# Mabee_DHT11_sensor_V1_1.net
KiCad netlist of a schematic drawn in EAGLE
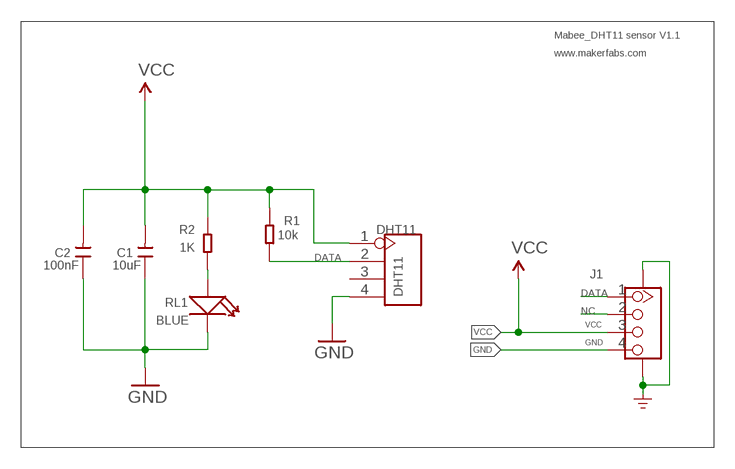
[diagram p0: schematic, sheet 1]

(export (version "E")
  (design (tool "Eeschema 10.0.6"))
  (components
    (comp (ref "C1")
      (value "10uF")
      (footprint "eagle-import:0603")
      (libsource (lib "eagle-import") (part "C-0603"))
    )
    (comp (ref "C2")
      (value "100nF")
      (footprint "eagle-import:0603")
      (libsource (lib "eagle-import") (part "C-0603"))
    )
    (comp (ref "DHT11")
      (value "DHT11")
      (footprint "eagle-import:4P-65_35ROUND")
      (libsource (lib "eagle-import") (part "HEADER-4P-60/35MILROUND"))
    )
    (comp (ref "J1")
      (value "GROVE-CONNECTOR-SMD'90D'")
      (footprint "eagle-import:HW4-SMD-2.0-90D")
      (libsource (lib "eagle-import") (part "GROVE-CONNECTOR-SMD'90D'"))
    )
    (comp (ref "R1")
      (value "10k")
      (footprint "eagle-import:R0603")
      (libsource (lib "eagle-import") (part "R-0603"))
    )
    (comp (ref "R2")
      (value "1K")
      (footprint "eagle-import:R0603")
      (libsource (lib "eagle-import") (part "R-0603"))
    )
    (comp (ref "RL1")
      (value "BLUE")
      (footprint "eagle-import:LED-0603")
      (libsource (lib "eagle-import") (part "LED'0603'"))
    )
  )
  (nets
    (net (code "1") (name "/DATA") (class "Default")
      (node (ref "DHT11") (pin "2") (pinfunction "P$2_2") (pintype "bidirectional"))
      (node (ref "J1") (pin "1") (pinfunction "1_1") (pintype "bidirectional"))
      (node (ref "R1") (pin "1") (pinfunction "1_1") (pintype "passive"))
    )
    (net (code "2") (name "/NC") (class "Default")
      (node (ref "J1") (pin "2") (pinfunction "2_2") (pintype "bidirectional"))
    )
    (net (code "3") (name "GND") (class "Default")
      (node (ref "C1") (pin "1") (pinfunction "1_1") (pintype "passive"))
      (node (ref "C2") (pin "1") (pinfunction "1_1") (pintype "passive"))
      (node (ref "DHT11") (pin "4") (pinfunction "P$4_4") (pintype "bidirectional"))
      (node (ref "J1") (pin "4") (pinfunction "4_4") (pintype "bidirectional"))
      (node (ref "J1") (pin "SS1") (pinfunction "SS1_SS1") (pintype "bidirectional"))
      (node (ref "J1") (pin "SS2") (pinfunction "SS2_SS2") (pintype "bidirectional"))
      (node (ref "RL1") (pin "-") (pinfunction "-_-") (pintype "passive"))
    )
    (net (code "4") (name "Net-(R2-Pad2)") (class "Default")
      (node (ref "R2") (pin "2") (pinfunction "2_2") (pintype "passive"))
      (node (ref "RL1") (pin "+") (pinfunction "+_+") (pintype "passive"))
    )
    (net (code "5") (name "VCC") (class "Default")
      (node (ref "C1") (pin "2") (pinfunction "2_2") (pintype "passive"))
      (node (ref "C2") (pin "2") (pinfunction "2_2") (pintype "passive"))
      (node (ref "DHT11") (pin "1") (pinfunction "P$1_1") (pintype "bidirectional"))
      (node (ref "J1") (pin "3") (pinfunction "3_3") (pintype "bidirectional"))
      (node (ref "R1") (pin "2") (pinfunction "2_2") (pintype "passive"))
      (node (ref "R2") (pin "1") (pinfunction "1_1") (pintype "passive"))
    )
    (net (code "6") (name "unconnected-(DHT11-P$3-Pad3)") (class "Default")
      (node (ref "DHT11") (pin "3") (pinfunction "P$3_3") (pintype "bidirectional"))
    )
  )
)
